# conditioning_circuit.net
KiCad netlist of a schematic drawn in Altium Designer
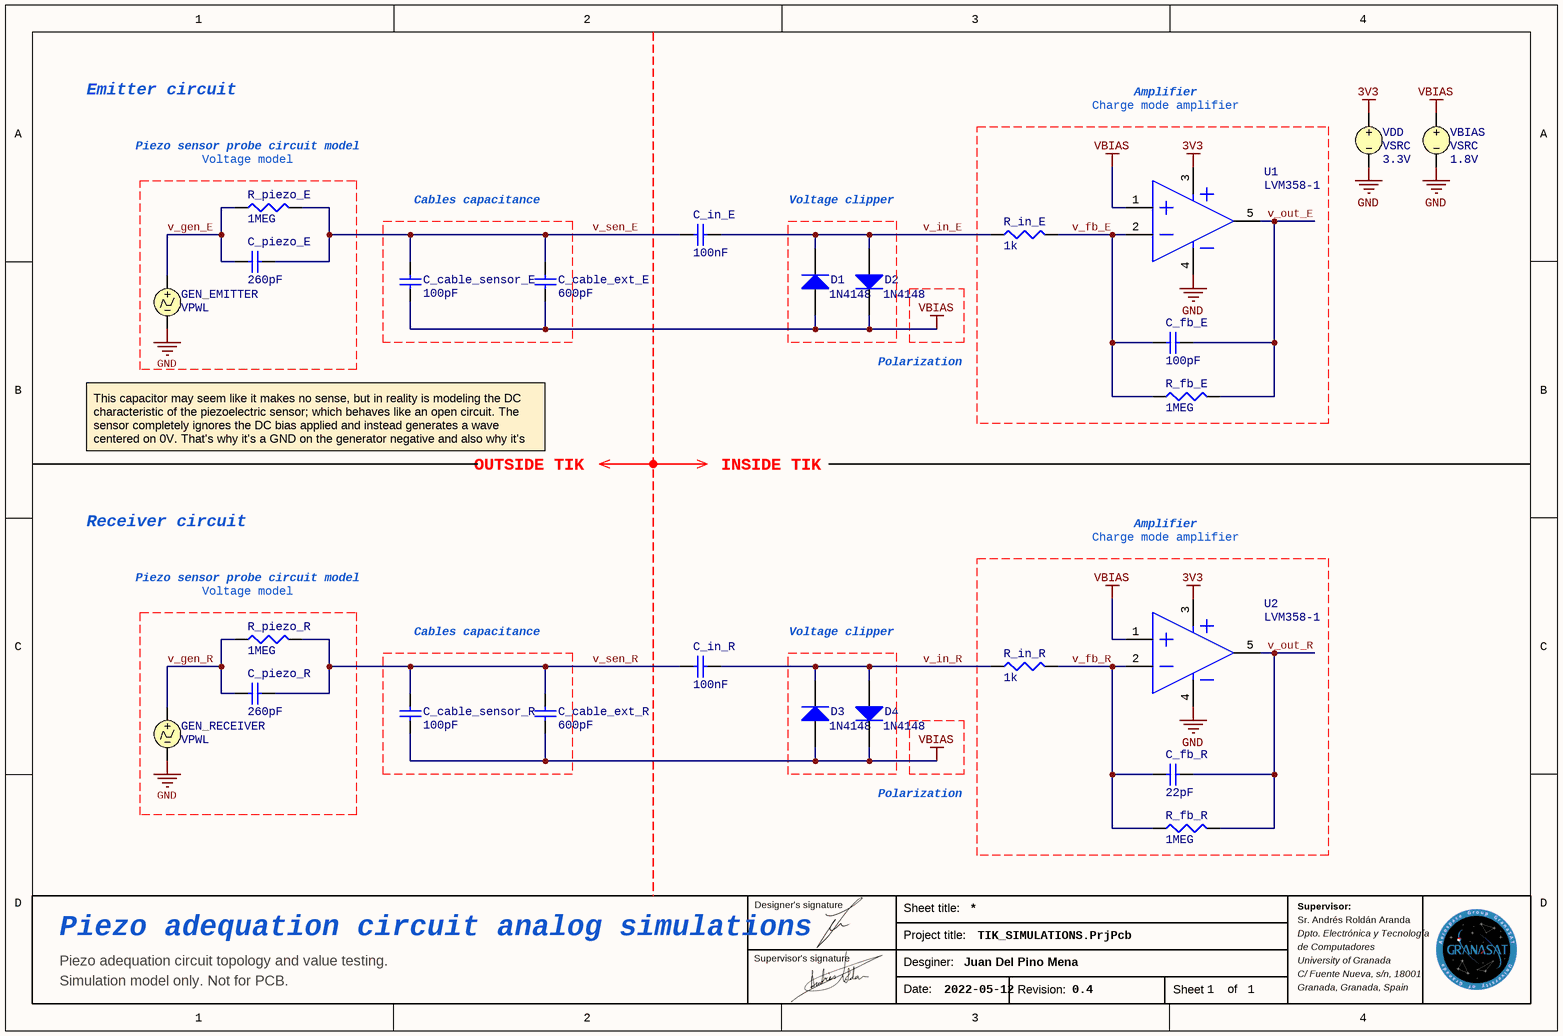
[diagram p0: conditioning_circuit.SchDoc]

(export (version "E")
  (design (tool "Eeschema 10.0.6"))
  (components
    (comp (ref "C_cable_ext_E")
      (value "600pF")
      (footprint "C1206")
      (description "Capacitor (Semiconductor SIM Model)")
      (fields (field (name "Comment") "Cap Semi") (field (name "PUBLISHER") "Altium Limited"))
      (libsource (lib "Miscellaneous Devices") (part "Cap Semi"))
    )
    (comp (ref "C_cable_ext_R")
      (value "600pF")
      (footprint "C1206")
      (description "Capacitor (Semiconductor SIM Model)")
      (fields (field (name "Comment") "Cap Semi") (field (name "PUBLISHER") "Altium Limited"))
      (libsource (lib "Miscellaneous Devices") (part "Cap Semi"))
    )
    (comp (ref "C_cable_sensor_E")
      (value "100pF")
      (footprint "C1206")
      (description "Capacitor (Semiconductor SIM Model)")
      (fields (field (name "Comment") "Cap Semi") (field (name "PUBLISHER") "Altium Limited"))
      (libsource (lib "Miscellaneous Devices") (part "Cap Semi"))
    )
    (comp (ref "C_cable_sensor_R")
      (value "100pF")
      (footprint "C1206")
      (description "Capacitor (Semiconductor SIM Model)")
      (fields (field (name "Comment") "Cap Semi") (field (name "PUBLISHER") "Altium Limited"))
      (libsource (lib "Miscellaneous Devices") (part "Cap Semi"))
    )
    (comp (ref "C_fb_E")
      (value "100pF")
      (footprint "C1206")
      (description "Capacitor (Semiconductor SIM Model)")
      (fields (field (name "Comment") "Cap Semi") (field (name "PUBLISHER") "Altium Limited"))
      (libsource (lib "Miscellaneous Devices") (part "Cap Semi"))
    )
    (comp (ref "C_fb_R")
      (value "22pF")
      (footprint "C1206")
      (description "Capacitor (Semiconductor SIM Model)")
      (fields (field (name "Comment") "Cap Semi") (field (name "PUBLISHER") "Altium Limited"))
      (libsource (lib "Miscellaneous Devices") (part "Cap Semi"))
    )
    (comp (ref "C_in_E")
      (value "100nF")
      (footprint "C1206")
      (description "Capacitor (Semiconductor SIM Model)")
      (fields (field (name "Comment") "Cap Semi") (field (name "PUBLISHER") "Altium Limited"))
      (libsource (lib "Miscellaneous Devices") (part "Cap Semi"))
    )
    (comp (ref "C_in_R")
      (value "100nF")
      (footprint "C1206")
      (description "Capacitor (Semiconductor SIM Model)")
      (fields (field (name "Comment") "Cap Semi") (field (name "PUBLISHER") "Altium Limited"))
      (libsource (lib "Miscellaneous Devices") (part "Cap Semi"))
    )
    (comp (ref "C_piezo_E")
      (value "260pF")
      (footprint "C1206")
      (description "Capacitor (Semiconductor SIM Model)")
      (fields (field (name "Comment") "Cap Semi") (field (name "PUBLISHER") "Altium Limited"))
      (libsource (lib "Miscellaneous Devices") (part "Cap Semi"))
    )
    (comp (ref "C_piezo_R")
      (value "260pF")
      (footprint "C1206")
      (description "Capacitor (Semiconductor SIM Model)")
      (fields (field (name "Comment") "Cap Semi") (field (name "PUBLISHER") "Altium Limited"))
      (libsource (lib "Miscellaneous Devices") (part "Cap Semi"))
    )
    (comp (ref "D1")
      (value "1N4148")
      (footprint "DO-35")
      (description "High Conductance Fast Diode")
      (fields (field (name "PUBLISHER") "Altium Limited"))
      (libsource (lib "Miscellaneous Devices") (part "Diode 1N4148"))
    )
    (comp (ref "D2")
      (value "1N4148")
      (footprint "DO-35")
      (description "High Conductance Fast Diode")
      (fields (field (name "PUBLISHER") "Altium Limited"))
      (libsource (lib "Miscellaneous Devices") (part "Diode 1N4148"))
    )
    (comp (ref "D3")
      (value "1N4148")
      (footprint "DO-35")
      (description "High Conductance Fast Diode")
      (fields (field (name "PUBLISHER") "Altium Limited"))
      (libsource (lib "Miscellaneous Devices") (part "Diode 1N4148"))
    )
    (comp (ref "D4")
      (value "1N4148")
      (footprint "DO-35")
      (description "High Conductance Fast Diode")
      (fields (field (name "PUBLISHER") "Altium Limited"))
      (libsource (lib "Miscellaneous Devices") (part "Diode 1N4148"))
    )
    (comp (ref "GEN_EMITTER")
      (value "VPWL")
      (description "Piecewise Linear Voltage Source")
      (fields (field (name "PUBLISHER") "Altium Limited"))
      (libsource (lib "Simulation Sources") (part "VPWL"))
    )
    (comp (ref "GEN_RECEIVER")
      (value "VPWL")
      (description "Piecewise Linear Voltage Source")
      (fields (field (name "PUBLISHER") "Altium Limited"))
      (libsource (lib "Simulation Sources") (part "VPWL"))
    )
    (comp (ref "R_fb_E")
      (value "1MEG")
      (footprint "J1-0603")
      (description "Resistor")
      (fields (field (name "Comment") "Res3") (field (name "PUBLISHER") "Altium Limited"))
      (libsource (lib "Miscellaneous Devices") (part "Res3"))
    )
    (comp (ref "R_fb_R")
      (value "1MEG")
      (footprint "J1-0603")
      (description "Resistor")
      (fields (field (name "Comment") "Res3") (field (name "PUBLISHER") "Altium Limited"))
      (libsource (lib "Miscellaneous Devices") (part "Res3"))
    )
    (comp (ref "R_in_E")
      (value "1k")
      (footprint "J1-0603")
      (description "Resistor")
      (fields (field (name "Comment") "Res3") (field (name "PUBLISHER") "Altium Limited"))
      (libsource (lib "Miscellaneous Devices") (part "Res3"))
    )
    (comp (ref "R_in_R")
      (value "1k")
      (footprint "J1-0603")
      (description "Resistor")
      (fields (field (name "Comment") "Res3") (field (name "PUBLISHER") "Altium Limited"))
      (libsource (lib "Miscellaneous Devices") (part "Res3"))
    )
    (comp (ref "R_piezo_E")
      (value "1MEG")
      (footprint "J1-0603")
      (description "Resistor")
      (fields (field (name "Comment") "Res3") (field (name "PUBLISHER") "Altium Limited"))
      (libsource (lib "Miscellaneous Devices") (part "Res3"))
    )
    (comp (ref "R_piezo_R")
      (value "1MEG")
      (footprint "J1-0603")
      (description "Resistor")
      (fields (field (name "Comment") "Res3") (field (name "PUBLISHER") "Altium Limited"))
      (libsource (lib "Miscellaneous Devices") (part "Res3"))
    )
    (comp (ref "U1")
      (value "LMV358")
      (fields (field (name "PART") "LVM358-1"))
      (libsource (lib "TIK_SIM") (part "LMV358"))
    )
    (comp (ref "U2")
      (value "LMV358")
      (fields (field (name "PART") "LVM358-1"))
      (libsource (lib "TIK_SIM") (part "LMV358"))
    )
    (comp (ref "VBIAS")
      (value "VSRC")
      (description "Voltage Source")
      (fields (field (name "ALTIUM_VALUE") "1.8V") (field (name "PUBLISHER") "Altium Limited"))
      (libsource (lib "Simulation Generic Components") (part "VSRC"))
    )
    (comp (ref "VDD")
      (value "VSRC")
      (description "Voltage Source")
      (fields (field (name "ALTIUM_VALUE") "3.3V") (field (name "PUBLISHER") "Altium Limited"))
      (libsource (lib "Simulation Generic Components") (part "VSRC"))
    )
  )
  (nets
    (net (code "1") (name "/v_fb_E") (class "Default")
      (node (ref "C_fb_E") (pin "1") (pinfunction "1_1") (pintype "passive"))
      (node (ref "R_fb_E") (pin "1") (pinfunction "1_1") (pintype "passive"))
      (node (ref "R_in_E") (pin "2") (pinfunction "2_2") (pintype "passive"))
      (node (ref "U1") (pin "2") (pinfunction "VIN-_2") (pintype "passive"))
    )
    (net (code "2") (name "/v_fb_R") (class "Default")
      (node (ref "C_fb_R") (pin "1") (pinfunction "1_1") (pintype "passive"))
      (node (ref "R_fb_R") (pin "1") (pinfunction "1_1") (pintype "passive"))
      (node (ref "R_in_R") (pin "2") (pinfunction "2_2") (pintype "passive"))
      (node (ref "U2") (pin "2") (pinfunction "VIN-_2") (pintype "passive"))
    )
    (net (code "3") (name "/v_gen_E") (class "Default")
      (node (ref "C_piezo_E") (pin "1") (pinfunction "1_1") (pintype "passive"))
      (node (ref "GEN_EMITTER") (pin "1") (pinfunction "1_1") (pintype "passive"))
      (node (ref "R_piezo_E") (pin "1") (pinfunction "1_1") (pintype "passive"))
    )
    (net (code "4") (name "/v_gen_R") (class "Default")
      (node (ref "C_piezo_R") (pin "1") (pinfunction "1_1") (pintype "passive"))
      (node (ref "GEN_RECEIVER") (pin "1") (pinfunction "1_1") (pintype "passive"))
      (node (ref "R_piezo_R") (pin "1") (pinfunction "1_1") (pintype "passive"))
    )
    (net (code "5") (name "/v_in_E") (class "Default")
      (node (ref "C_in_E") (pin "2") (pinfunction "2_2") (pintype "passive"))
      (node (ref "D1") (pin "2") (pinfunction "K_2") (pintype "passive"))
      (node (ref "D2") (pin "1") (pinfunction "A_1") (pintype "passive"))
      (node (ref "R_in_E") (pin "1") (pinfunction "1_1") (pintype "passive"))
    )
    (net (code "6") (name "/v_in_R") (class "Default")
      (node (ref "C_in_R") (pin "2") (pinfunction "2_2") (pintype "passive"))
      (node (ref "D3") (pin "2") (pinfunction "K_2") (pintype "passive"))
      (node (ref "D4") (pin "1") (pinfunction "A_1") (pintype "passive"))
      (node (ref "R_in_R") (pin "1") (pinfunction "1_1") (pintype "passive"))
    )
    (net (code "7") (name "/v_out_E") (class "Default")
      (node (ref "C_fb_E") (pin "2") (pinfunction "2_2") (pintype "passive"))
      (node (ref "R_fb_E") (pin "2") (pinfunction "2_2") (pintype "passive"))
      (node (ref "U1") (pin "5") (pinfunction "VOUT_5") (pintype "passive"))
    )
    (net (code "8") (name "/v_out_R") (class "Default")
      (node (ref "C_fb_R") (pin "2") (pinfunction "2_2") (pintype "passive"))
      (node (ref "R_fb_R") (pin "2") (pinfunction "2_2") (pintype "passive"))
      (node (ref "U2") (pin "5") (pinfunction "VOUT_5") (pintype "passive"))
    )
    (net (code "9") (name "/v_sen_E") (class "Default")
      (node (ref "C_cable_ext_E") (pin "2") (pinfunction "2_2") (pintype "passive"))
      (node (ref "C_cable_sensor_E") (pin "2") (pinfunction "2_2") (pintype "passive"))
      (node (ref "C_in_E") (pin "1") (pinfunction "1_1") (pintype "passive"))
      (node (ref "C_piezo_E") (pin "2") (pinfunction "2_2") (pintype "passive"))
      (node (ref "R_piezo_E") (pin "2") (pinfunction "2_2") (pintype "passive"))
    )
    (net (code "10") (name "/v_sen_R") (class "Default")
      (node (ref "C_cable_ext_R") (pin "2") (pinfunction "2_2") (pintype "passive"))
      (node (ref "C_cable_sensor_R") (pin "2") (pinfunction "2_2") (pintype "passive"))
      (node (ref "C_in_R") (pin "1") (pinfunction "1_1") (pintype "passive"))
      (node (ref "C_piezo_R") (pin "2") (pinfunction "2_2") (pintype "passive"))
      (node (ref "R_piezo_R") (pin "2") (pinfunction "2_2") (pintype "passive"))
    )
    (net (code "11") (name "3V3") (class "Default")
      (node (ref "U1") (pin "3") (pinfunction "VSUP+_3") (pintype "passive"))
      (node (ref "U2") (pin "3") (pinfunction "VSUP+_3") (pintype "passive"))
      (node (ref "VDD") (pin "1") (pinfunction "1_1") (pintype "passive"))
    )
    (net (code "12") (name "GND") (class "Default")
      (node (ref "GEN_EMITTER") (pin "2") (pinfunction "2_2") (pintype "passive"))
      (node (ref "GEN_RECEIVER") (pin "2") (pinfunction "2_2") (pintype "passive"))
      (node (ref "U1") (pin "4") (pinfunction "VSUP-_4") (pintype "passive"))
      (node (ref "U2") (pin "4") (pinfunction "VSUP-_4") (pintype "passive"))
      (node (ref "VBIAS") (pin "2") (pinfunction "2_2") (pintype "passive"))
      (node (ref "VDD") (pin "2") (pinfunction "2_2") (pintype "passive"))
    )
    (net (code "13") (name "VBIAS") (class "Default")
      (node (ref "C_cable_ext_E") (pin "1") (pinfunction "1_1") (pintype "passive"))
      (node (ref "C_cable_ext_R") (pin "1") (pinfunction "1_1") (pintype "passive"))
      (node (ref "C_cable_sensor_E") (pin "1") (pinfunction "1_1") (pintype "passive"))
      (node (ref "C_cable_sensor_R") (pin "1") (pinfunction "1_1") (pintype "passive"))
      (node (ref "D1") (pin "1") (pinfunction "A_1") (pintype "passive"))
      (node (ref "D2") (pin "2") (pinfunction "K_2") (pintype "passive"))
      (node (ref "D3") (pin "1") (pinfunction "A_1") (pintype "passive"))
      (node (ref "D4") (pin "2") (pinfunction "K_2") (pintype "passive"))
      (node (ref "U1") (pin "1") (pinfunction "VIN+_1") (pintype "passive"))
      (node (ref "U2") (pin "1") (pinfunction "VIN+_1") (pintype "passive"))
      (node (ref "VBIAS") (pin "1") (pinfunction "1_1") (pintype "passive"))
    )
  )
)
